# a2401-diode-distortion.net
KiCad netlist of a schematic drawn in EAGLE
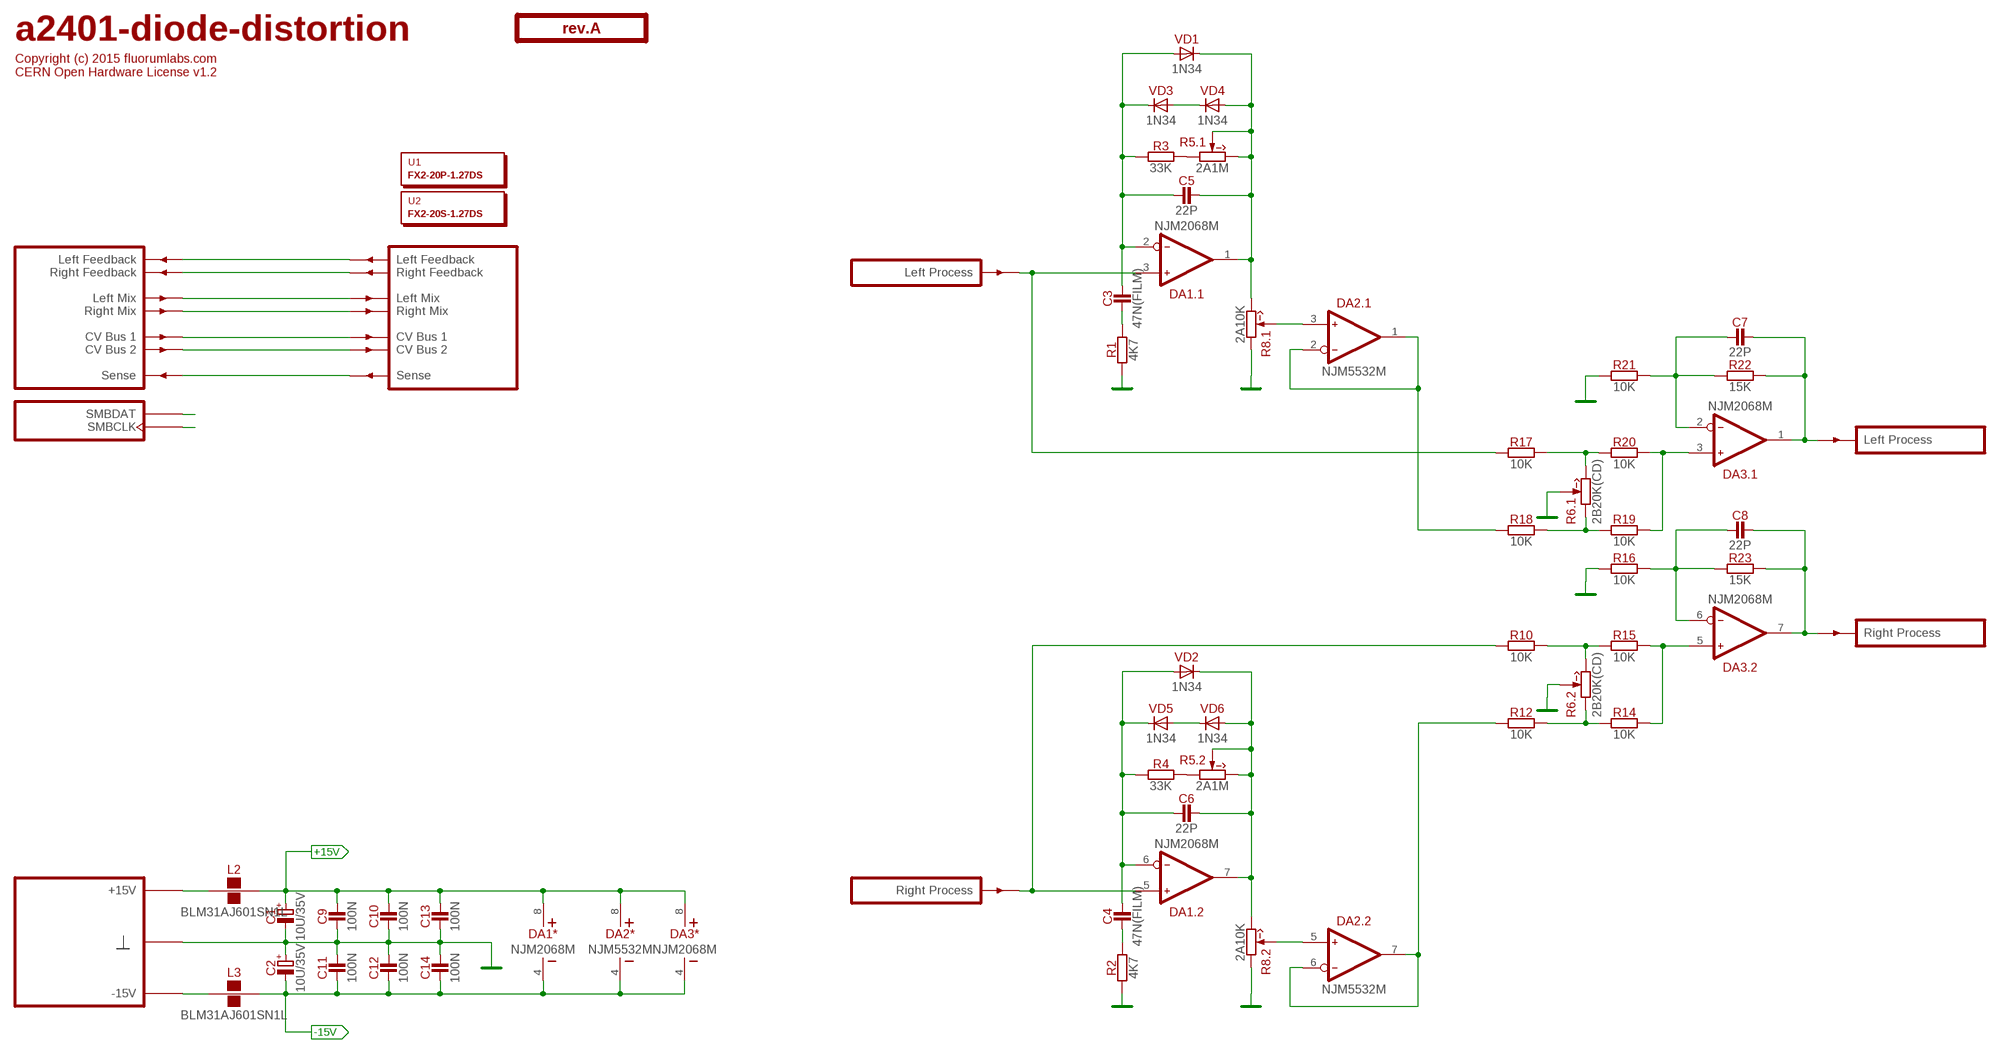
[diagram p0: schematic, sheet 1]

(export (version "E")
  (design (tool "Eeschema 10.0.6"))
  (components
    (comp (ref "C1")
      (value "10U/35V")
      (footprint "eagle-import:E2-5")
      (libsource (lib "eagle-import") (part "?10U/35V"))
    )
    (comp (ref "C2")
      (value "10U/35V")
      (footprint "eagle-import:E2-5")
      (libsource (lib "eagle-import") (part "?10U/35V"))
    )
    (comp (ref "C3")
      (value "47N(FILM)")
      (footprint "eagle-import:C050-025X075")
      (libsource (lib "eagle-import") (part "?47N(FILM)"))
    )
    (comp (ref "C4")
      (value "47N(FILM)")
      (footprint "eagle-import:C050-025X075")
      (libsource (lib "eagle-import") (part "?47N(FILM)"))
    )
    (comp (ref "C5")
      (value "22P")
      (footprint "eagle-import:C-0805")
      (libsource (lib "eagle-import") (part "?22P"))
    )
    (comp (ref "C6")
      (value "22P")
      (footprint "eagle-import:C-0805")
      (libsource (lib "eagle-import") (part "?22P"))
    )
    (comp (ref "C7")
      (value "22P")
      (footprint "eagle-import:C-0805")
      (libsource (lib "eagle-import") (part "?22P"))
    )
    (comp (ref "C8")
      (value "22P")
      (footprint "eagle-import:C-0805")
      (libsource (lib "eagle-import") (part "?22P"))
    )
    (comp (ref "C9")
      (value "100N")
      (footprint "eagle-import:C-0805")
      (libsource (lib "eagle-import") (part "?100N"))
    )
    (comp (ref "C10")
      (value "100N")
      (footprint "eagle-import:C-0805")
      (libsource (lib "eagle-import") (part "?100N"))
    )
    (comp (ref "C11")
      (value "100N")
      (footprint "eagle-import:C-0805")
      (libsource (lib "eagle-import") (part "?100N"))
    )
    (comp (ref "C12")
      (value "100N")
      (footprint "eagle-import:C-0805")
      (libsource (lib "eagle-import") (part "?100N"))
    )
    (comp (ref "C13")
      (value "100N")
      (footprint "eagle-import:C-0805")
      (libsource (lib "eagle-import") (part "?100N"))
    )
    (comp (ref "C14")
      (value "100N")
      (footprint "eagle-import:C-0805")
      (libsource (lib "eagle-import") (part "?100N"))
    )
    (comp (ref "DA1")
      (value "NJM2068M")
      (footprint "eagle-import:SO-8")
      (libsource (lib "eagle-import") (part "NJM2068M"))
    )
    (comp (ref "DA2")
      (value "NJM5532M")
      (footprint "eagle-import:SO-8")
      (libsource (lib "eagle-import") (part "NJM5532M"))
    )
    (comp (ref "DA3")
      (value "NJM2068M")
      (footprint "eagle-import:SO-8")
      (libsource (lib "eagle-import") (part "NJM2068M"))
    )
    (comp (ref "L2")
      (value "BLM31AJ601SN1L")
      (footprint "eagle-import:1206")
      (libsource (lib "eagle-import") (part "BLM31AJ601SN1L"))
    )
    (comp (ref "L3")
      (value "BLM31AJ601SN1L")
      (footprint "eagle-import:1206")
      (libsource (lib "eagle-import") (part "BLM31AJ601SN1L"))
    )
    (comp (ref "O1")
      (value "TITLE")
      (footprint "eagle-import:EMPTY")
      (libsource (lib "eagle-import") (part "TITLE"))
    )
    (comp (ref "PCB1")
      (value "rev.A")
      (footprint "eagle-import:ST2-BOARD-50")
      (libsource (lib "eagle-import") (part "ST2-BOARD-50"))
    )
    (comp (ref "R1")
      (value "4K7")
      (footprint "eagle-import:R-0805")
      (libsource (lib "eagle-import") (part "?4K7"))
    )
    (comp (ref "R2")
      (value "4K7")
      (footprint "eagle-import:R-0805")
      (libsource (lib "eagle-import") (part "?4K7"))
    )
    (comp (ref "R3")
      (value "33K")
      (footprint "eagle-import:R-0805")
      (libsource (lib "eagle-import") (part "?33K"))
    )
    (comp (ref "R4")
      (value "33K")
      (footprint "eagle-import:R-0805")
      (libsource (lib "eagle-import") (part "?33K"))
    )
    (comp (ref "R5")
      (value "2A1M")
      (footprint "eagle-import:RV11-DUAL")
      (libsource (lib "eagle-import") (part "2?A1M"))
    )
    (comp (ref "R6")
      (value "2B20K(CD)")
      (footprint "eagle-import:RV11-DUAL")
      (libsource (lib "eagle-import") (part "2?B20K(CD)"))
    )
    (comp (ref "R8")
      (value "2A10K")
      (footprint "eagle-import:RV11-DUAL")
      (libsource (lib "eagle-import") (part "2?A10K"))
    )
    (comp (ref "R10")
      (value "10K")
      (footprint "eagle-import:R-0805")
      (libsource (lib "eagle-import") (part "?10K"))
    )
    (comp (ref "R12")
      (value "10K")
      (footprint "eagle-import:R-0805")
      (libsource (lib "eagle-import") (part "?10K"))
    )
    (comp (ref "R14")
      (value "10K")
      (footprint "eagle-import:R-0805")
      (libsource (lib "eagle-import") (part "?10K"))
    )
    (comp (ref "R15")
      (value "10K")
      (footprint "eagle-import:R-0805")
      (libsource (lib "eagle-import") (part "?10K"))
    )
    (comp (ref "R16")
      (value "10K")
      (footprint "eagle-import:R-0805")
      (libsource (lib "eagle-import") (part "?10K"))
    )
    (comp (ref "R17")
      (value "10K")
      (footprint "eagle-import:R-0805")
      (libsource (lib "eagle-import") (part "?10K"))
    )
    (comp (ref "R18")
      (value "10K")
      (footprint "eagle-import:R-0805")
      (libsource (lib "eagle-import") (part "?10K"))
    )
    (comp (ref "R19")
      (value "10K")
      (footprint "eagle-import:R-0805")
      (libsource (lib "eagle-import") (part "?10K"))
    )
    (comp (ref "R20")
      (value "10K")
      (footprint "eagle-import:R-0805")
      (libsource (lib "eagle-import") (part "?10K"))
    )
    (comp (ref "R21")
      (value "10K")
      (footprint "eagle-import:R-0805")
      (libsource (lib "eagle-import") (part "?10K"))
    )
    (comp (ref "R22")
      (value "15K")
      (footprint "eagle-import:R-0805")
      (libsource (lib "eagle-import") (part "?15K"))
    )
    (comp (ref "R23")
      (value "15K")
      (footprint "eagle-import:R-0805")
      (libsource (lib "eagle-import") (part "?15K"))
    )
    (comp (ref "U1")
      (value "FX2-20P-1.27DS")
      (footprint "eagle-import:EMPTY")
      (libsource (lib "eagle-import") (part "?FX2-20P-1.27DS"))
    )
    (comp (ref "U2")
      (value "FX2-20S-1.27DS")
      (footprint "eagle-import:EMPTY")
      (libsource (lib "eagle-import") (part "?FX2-20S-1.27DS"))
    )
    (comp (ref "VD1")
      (value "1N34")
      (footprint "eagle-import:DO35-15")
      (libsource (lib "eagle-import") (part "?1N34"))
    )
    (comp (ref "VD2")
      (value "1N34")
      (footprint "eagle-import:DO35-15")
      (libsource (lib "eagle-import") (part "?1N34"))
    )
    (comp (ref "VD3")
      (value "1N34")
      (footprint "eagle-import:DO35-15")
      (libsource (lib "eagle-import") (part "?1N34"))
    )
    (comp (ref "VD4")
      (value "1N34")
      (footprint "eagle-import:DO35-15")
      (libsource (lib "eagle-import") (part "?1N34"))
    )
    (comp (ref "VD5")
      (value "1N34")
      (footprint "eagle-import:DO35-15")
      (libsource (lib "eagle-import") (part "?1N34"))
    )
    (comp (ref "VD6")
      (value "1N34")
      (footprint "eagle-import:DO35-15")
      (libsource (lib "eagle-import") (part "?1N34"))
    )
  )
  (nets
    (net (code "1") (name "+15V") (class "Default")
      (node (ref "C1") (pin "+") (pinfunction "+_+") (pintype "passive"))
      (node (ref "C10") (pin "2") (pinfunction "2_2") (pintype "passive"))
      (node (ref "C13") (pin "2") (pinfunction "2_2") (pintype "passive"))
      (node (ref "C9") (pin "2") (pinfunction "2_2") (pintype "passive"))
      (node (ref "DA1") (pin "8") (pinfunction "V+_8") (pintype "power_in"))
      (node (ref "DA2") (pin "8") (pinfunction "V+_8") (pintype "power_in"))
      (node (ref "DA3") (pin "8") (pinfunction "V+_8") (pintype "power_in"))
      (node (ref "L2") (pin "2") (pinfunction "2_2") (pintype "passive"))
    )
    (net (code "2") (name "-15V") (class "Default")
      (node (ref "C11") (pin "1") (pinfunction "1_1") (pintype "passive"))
      (node (ref "C12") (pin "1") (pinfunction "1_1") (pintype "passive"))
      (node (ref "C14") (pin "1") (pinfunction "1_1") (pintype "passive"))
      (node (ref "C2") (pin "-") (pinfunction "-_-") (pintype "passive"))
      (node (ref "DA1") (pin "4") (pinfunction "V-_4") (pintype "power_in"))
      (node (ref "DA2") (pin "4") (pinfunction "V-_4") (pintype "power_in"))
      (node (ref "DA3") (pin "4") (pinfunction "V-_4") (pintype "power_in"))
      (node (ref "L3") (pin "2") (pinfunction "2_2") (pintype "passive"))
    )
    (net (code "3") (name "GND") (class "Default")
      (node (ref "C1") (pin "-") (pinfunction "-_-") (pintype "passive"))
      (node (ref "C10") (pin "1") (pinfunction "1_1") (pintype "passive"))
      (node (ref "C11") (pin "2") (pinfunction "2_2") (pintype "passive"))
      (node (ref "C12") (pin "2") (pinfunction "2_2") (pintype "passive"))
      (node (ref "C13") (pin "1") (pinfunction "1_1") (pintype "passive"))
      (node (ref "C14") (pin "2") (pinfunction "2_2") (pintype "passive"))
      (node (ref "C2") (pin "+") (pinfunction "+_+") (pintype "passive"))
      (node (ref "C9") (pin "1") (pinfunction "1_1") (pintype "passive"))
      (node (ref "PCB1") (pin "B4") (pinfunction "GND_B4") (pintype "bidirectional"))
      (node (ref "PCB1") (pin "B4'") (pinfunction "GND_B4'") (pintype "bidirectional"))
      (node (ref "PCB1") (pin "B5") (pinfunction "GND_B5") (pintype "bidirectional"))
      (node (ref "PCB1") (pin "B5'") (pinfunction "GND_B5'") (pintype "bidirectional"))
      (node (ref "PCB1") (pin "B6") (pinfunction "GND_B6") (pintype "bidirectional"))
      (node (ref "PCB1") (pin "B6'") (pinfunction "GND_B6'") (pintype "bidirectional"))
      (node (ref "PCB1") (pin "B7") (pinfunction "GND_B7") (pintype "bidirectional"))
      (node (ref "PCB1") (pin "B7'") (pinfunction "GND_B7'") (pintype "bidirectional"))
      (node (ref "PCB1") (pin "B8") (pinfunction "GND_B8") (pintype "bidirectional"))
      (node (ref "PCB1") (pin "B8'") (pinfunction "GND_B8'") (pintype "bidirectional"))
      (node (ref "R1") (pin "1") (pinfunction "1_1") (pintype "passive"))
      (node (ref "R16") (pin "1") (pinfunction "1_1") (pintype "passive"))
      (node (ref "R2") (pin "1") (pinfunction "1_1") (pintype "passive"))
      (node (ref "R21") (pin "1") (pinfunction "1_1") (pintype "passive"))
      (node (ref "R6") (pin "2") (pinfunction "W_2") (pintype "passive"))
      (node (ref "R6") (pin "2'") (pinfunction "W_2'") (pintype "passive"))
      (node (ref "R8") (pin "1") (pinfunction "CCW_1") (pintype "passive"))
      (node (ref "R8") (pin "1'") (pinfunction "CCW_1'") (pintype "passive"))
    )
    (net (code "4") (name "Net-(C3-Pad1)") (class "Default")
      (node (ref "C3") (pin "1") (pinfunction "1_1") (pintype "passive"))
      (node (ref "R1") (pin "2") (pinfunction "2_2") (pintype "passive"))
    )
    (net (code "5") (name "Net-(C4-Pad1)") (class "Default")
      (node (ref "C4") (pin "1") (pinfunction "1_1") (pintype "passive"))
      (node (ref "R2") (pin "2") (pinfunction "2_2") (pintype "passive"))
    )
    (net (code "6") (name "Net-(DA1B-IN+)") (class "Default")
      (node (ref "DA1") (pin "3") (pinfunction "IN+_3") (pintype "input"))
      (node (ref "PCB1") (pin "BINL") (pinfunction "INL_BINL") (pintype "bidirectional"))
      (node (ref "R17") (pin "1") (pinfunction "1_1") (pintype "passive"))
    )
    (net (code "7") (name "Net-(DA1B-IN-)") (class "Default")
      (node (ref "C3") (pin "2") (pinfunction "2_2") (pintype "passive"))
      (node (ref "C5") (pin "1") (pinfunction "1_1") (pintype "passive"))
      (node (ref "DA1") (pin "2") (pinfunction "IN-_2") (pintype "input"))
      (node (ref "R3") (pin "1") (pinfunction "1_1") (pintype "passive"))
      (node (ref "VD1") (pin "A") (pinfunction "A_A") (pintype "passive"))
      (node (ref "VD3") (pin "C") (pinfunction "C_C") (pintype "passive"))
    )
    (net (code "8") (name "Net-(DA1B-OUT)") (class "Default")
      (node (ref "C5") (pin "2") (pinfunction "2_2") (pintype "passive"))
      (node (ref "DA1") (pin "1") (pinfunction "OUT_1") (pintype "output"))
      (node (ref "R5") (pin "2") (pinfunction "W_2") (pintype "passive"))
      (node (ref "R5") (pin "3") (pinfunction "CW_3") (pintype "passive"))
      (node (ref "R8") (pin "3") (pinfunction "CW_3") (pintype "passive"))
      (node (ref "VD1") (pin "C") (pinfunction "C_C") (pintype "passive"))
      (node (ref "VD4") (pin "A") (pinfunction "A_A") (pintype "passive"))
    )
    (net (code "9") (name "Net-(DA1C-IN+)") (class "Default")
      (node (ref "DA1") (pin "5") (pinfunction "IN+_5") (pintype "input"))
      (node (ref "PCB1") (pin "BINR") (pinfunction "INR_BINR") (pintype "bidirectional"))
      (node (ref "R10") (pin "1") (pinfunction "1_1") (pintype "passive"))
    )
    (net (code "10") (name "Net-(DA1C-IN-)") (class "Default")
      (node (ref "C4") (pin "2") (pinfunction "2_2") (pintype "passive"))
      (node (ref "C6") (pin "1") (pinfunction "1_1") (pintype "passive"))
      (node (ref "DA1") (pin "6") (pinfunction "IN-_6") (pintype "input"))
      (node (ref "R4") (pin "1") (pinfunction "1_1") (pintype "passive"))
      (node (ref "VD2") (pin "A") (pinfunction "A_A") (pintype "passive"))
      (node (ref "VD5") (pin "C") (pinfunction "C_C") (pintype "passive"))
    )
    (net (code "11") (name "Net-(DA1C-OUT)") (class "Default")
      (node (ref "C6") (pin "2") (pinfunction "2_2") (pintype "passive"))
      (node (ref "DA1") (pin "7") (pinfunction "OUT_7") (pintype "output"))
      (node (ref "R5") (pin "2'") (pinfunction "W_2'") (pintype "passive"))
      (node (ref "R5") (pin "3'") (pinfunction "CW_3'") (pintype "passive"))
      (node (ref "R8") (pin "3'") (pinfunction "CW_3'") (pintype "passive"))
      (node (ref "VD2") (pin "C") (pinfunction "C_C") (pintype "passive"))
      (node (ref "VD6") (pin "A") (pinfunction "A_A") (pintype "passive"))
    )
    (net (code "12") (name "Net-(DA2B-IN+)") (class "Default")
      (node (ref "DA2") (pin "3") (pinfunction "IN+_3") (pintype "input"))
      (node (ref "R8") (pin "2") (pinfunction "W_2") (pintype "passive"))
    )
    (net (code "13") (name "Net-(DA2B-IN-)") (class "Default")
      (node (ref "DA2") (pin "1") (pinfunction "OUT_1") (pintype "output"))
      (node (ref "DA2") (pin "2") (pinfunction "IN-_2") (pintype "input"))
      (node (ref "R18") (pin "1") (pinfunction "1_1") (pintype "passive"))
    )
    (net (code "14") (name "Net-(DA2C-IN+)") (class "Default")
      (node (ref "DA2") (pin "5") (pinfunction "IN+_5") (pintype "input"))
      (node (ref "R8") (pin "2'") (pinfunction "W_2'") (pintype "passive"))
    )
    (net (code "15") (name "Net-(DA2C-IN-)") (class "Default")
      (node (ref "DA2") (pin "6") (pinfunction "IN-_6") (pintype "input"))
      (node (ref "DA2") (pin "7") (pinfunction "OUT_7") (pintype "output"))
      (node (ref "R12") (pin "1") (pinfunction "1_1") (pintype "passive"))
    )
    (net (code "16") (name "Net-(DA3B-IN+)") (class "Default")
      (node (ref "DA3") (pin "3") (pinfunction "IN+_3") (pintype "input"))
      (node (ref "R19") (pin "2") (pinfunction "2_2") (pintype "passive"))
      (node (ref "R20") (pin "2") (pinfunction "2_2") (pintype "passive"))
    )
    (net (code "17") (name "Net-(DA3B-IN-)") (class "Default")
      (node (ref "C7") (pin "1") (pinfunction "1_1") (pintype "passive"))
      (node (ref "DA3") (pin "2") (pinfunction "IN-_2") (pintype "input"))
      (node (ref "R21") (pin "2") (pinfunction "2_2") (pintype "passive"))
      (node (ref "R22") (pin "1") (pinfunction "1_1") (pintype "passive"))
    )
    (net (code "18") (name "Net-(DA3B-OUT)") (class "Default")
      (node (ref "C7") (pin "2") (pinfunction "2_2") (pintype "passive"))
      (node (ref "DA3") (pin "1") (pinfunction "OUT_1") (pintype "output"))
      (node (ref "PCB1") (pin "BOUTL'") (pinfunction "OUTL_BOUTL'") (pintype "bidirectional"))
      (node (ref "R22") (pin "2") (pinfunction "2_2") (pintype "passive"))
    )
    (net (code "19") (name "Net-(DA3C-IN+)") (class "Default")
      (node (ref "DA3") (pin "5") (pinfunction "IN+_5") (pintype "input"))
      (node (ref "R14") (pin "2") (pinfunction "2_2") (pintype "passive"))
      (node (ref "R15") (pin "2") (pinfunction "2_2") (pintype "passive"))
    )
    (net (code "20") (name "Net-(DA3C-IN-)") (class "Default")
      (node (ref "C8") (pin "1") (pinfunction "1_1") (pintype "passive"))
      (node (ref "DA3") (pin "6") (pinfunction "IN-_6") (pintype "input"))
      (node (ref "R16") (pin "2") (pinfunction "2_2") (pintype "passive"))
      (node (ref "R23") (pin "1") (pinfunction "1_1") (pintype "passive"))
    )
    (net (code "21") (name "Net-(DA3C-OUT)") (class "Default")
      (node (ref "C8") (pin "2") (pinfunction "2_2") (pintype "passive"))
      (node (ref "DA3") (pin "7") (pinfunction "OUT_7") (pintype "output"))
      (node (ref "PCB1") (pin "BOUTR'") (pinfunction "OUTR_BOUTR'") (pintype "bidirectional"))
      (node (ref "R23") (pin "2") (pinfunction "2_2") (pintype "passive"))
    )
    (net (code "22") (name "Net-(L2-Pad1)") (class "Default")
      (node (ref "L2") (pin "1") (pinfunction "1_1") (pintype "passive"))
      (node (ref "PCB1") (pin "A+15") (pinfunction "P+15V_A+15") (pintype "bidirectional"))
      (node (ref "PCB1") (pin "A+15'") (pinfunction "P+15V_A+15'") (pintype "bidirectional"))
      (node (ref "PCB1") (pin "B+15") (pinfunction "P+15V_B+15") (pintype "bidirectional"))
      (node (ref "PCB1") (pin "B+15'") (pinfunction "P+15V_B+15'") (pintype "bidirectional"))
    )
    (net (code "23") (name "Net-(L3-Pad1)") (class "Default")
      (node (ref "L3") (pin "1") (pinfunction "1_1") (pintype "passive"))
      (node (ref "PCB1") (pin "A-15") (pinfunction "P-15V_A-15") (pintype "bidirectional"))
      (node (ref "PCB1") (pin "A-15'") (pinfunction "P-15V_A-15'") (pintype "bidirectional"))
      (node (ref "PCB1") (pin "B-15") (pinfunction "P-15V_B-15") (pintype "bidirectional"))
      (node (ref "PCB1") (pin "B-15'") (pinfunction "P-15V_B-15'") (pintype "bidirectional"))
    )
    (net (code "24") (name "Net-(PCB1F-CV1)") (class "Default")
      (node (ref "PCB1") (pin "ACV1") (pinfunction "CV1_ACV1") (pintype "bidirectional"))
      (node (ref "PCB1") (pin "ACV1'") (pinfunction "CV1'_ACV1'") (pintype "bidirectional"))
    )
    (net (code "25") (name "Net-(PCB1F-CV2)") (class "Default")
      (node (ref "PCB1") (pin "ACV2") (pinfunction "CV2_ACV2") (pintype "bidirectional"))
      (node (ref "PCB1") (pin "ACV2'") (pinfunction "CV2'_ACV2'") (pintype "bidirectional"))
    )
    (net (code "26") (name "Net-(PCB1F-LFBK)") (class "Default")
      (node (ref "PCB1") (pin "ALFBK") (pinfunction "LFBK_ALFBK") (pintype "bidirectional"))
      (node (ref "PCB1") (pin "ALFBK'") (pinfunction "LFBK'_ALFBK'") (pintype "bidirectional"))
    )
    (net (code "27") (name "Net-(PCB1F-LMIX)") (class "Default")
      (node (ref "PCB1") (pin "ALMIX") (pinfunction "LMIX_ALMIX") (pintype "bidirectional"))
      (node (ref "PCB1") (pin "ALMIX'") (pinfunction "LMIX'_ALMIX'") (pintype "bidirectional"))
    )
    (net (code "28") (name "Net-(PCB1F-RFBK)") (class "Default")
      (node (ref "PCB1") (pin "ARFBK") (pinfunction "RFBK_ARFBK") (pintype "bidirectional"))
      (node (ref "PCB1") (pin "ARFBK'") (pinfunction "RFBK'_ARFBK'") (pintype "bidirectional"))
    )
    (net (code "29") (name "Net-(PCB1F-RMIX)") (class "Default")
      (node (ref "PCB1") (pin "ARMIX") (pinfunction "RMIX_ARMIX") (pintype "bidirectional"))
      (node (ref "PCB1") (pin "ARMIX'") (pinfunction "RMIX'_ARMIX'") (pintype "bidirectional"))
    )
    (net (code "30") (name "Net-(PCB1F-SENSE)") (class "Default")
      (node (ref "PCB1") (pin "BSENSE") (pinfunction "SENSE_BSENSE") (pintype "bidirectional"))
      (node (ref "PCB1") (pin "BSENSE'") (pinfunction "SENSE'_BSENSE'") (pintype "bidirectional"))
    )
    (net (code "31") (name "Net-(PCB1H-SMBCLK-PadASMBCLK')") (class "Default")
      (node (ref "PCB1") (pin "ASMBCLK") (pinfunction "SMBCLK_ASMBCLK") (pintype "bidirectional"))
      (node (ref "PCB1") (pin "ASMBCLK'") (pinfunction "SMBCLK_ASMBCLK'") (pintype "bidirectional"))
    )
    (net (code "32") (name "Net-(PCB1H-SMBDAT-PadASMBDAT')") (class "Default")
      (node (ref "PCB1") (pin "ASMBDAT") (pinfunction "SMBDAT_ASMBDAT") (pintype "bidirectional"))
      (node (ref "PCB1") (pin "ASMBDAT'") (pinfunction "SMBDAT_ASMBDAT'") (pintype "bidirectional"))
    )
    (net (code "33") (name "Net-(R5A-CCW)") (class "Default")
      (node (ref "R3") (pin "2") (pinfunction "2_2") (pintype "passive"))
      (node (ref "R5") (pin "1") (pinfunction "CCW_1") (pintype "passive"))
    )
    (net (code "34") (name "Net-(R5B-CCW)") (class "Default")
      (node (ref "R4") (pin "2") (pinfunction "2_2") (pintype "passive"))
      (node (ref "R5") (pin "1'") (pinfunction "CCW_1'") (pintype "passive"))
    )
    (net (code "35") (name "Net-(R6A-CCW)") (class "Default")
      (node (ref "R18") (pin "2") (pinfunction "2_2") (pintype "passive"))
      (node (ref "R19") (pin "1") (pinfunction "1_1") (pintype "passive"))
      (node (ref "R6") (pin "1") (pinfunction "CCW_1") (pintype "passive"))
    )
    (net (code "36") (name "Net-(R6A-CW)") (class "Default")
      (node (ref "R17") (pin "2") (pinfunction "2_2") (pintype "passive"))
      (node (ref "R20") (pin "1") (pinfunction "1_1") (pintype "passive"))
      (node (ref "R6") (pin "3") (pinfunction "CW_3") (pintype "passive"))
    )
    (net (code "37") (name "Net-(R6B-CCW)") (class "Default")
      (node (ref "R12") (pin "2") (pinfunction "2_2") (pintype "passive"))
      (node (ref "R14") (pin "1") (pinfunction "1_1") (pintype "passive"))
      (node (ref "R6") (pin "1'") (pinfunction "CCW_1'") (pintype "passive"))
    )
    (net (code "38") (name "Net-(R6B-CW)") (class "Default")
      (node (ref "R10") (pin "2") (pinfunction "2_2") (pintype "passive"))
      (node (ref "R15") (pin "1") (pinfunction "1_1") (pintype "passive"))
      (node (ref "R6") (pin "3'") (pinfunction "CW_3'") (pintype "passive"))
    )
    (net (code "39") (name "Net-(VD3-PadA)") (class "Default")
      (node (ref "VD3") (pin "A") (pinfunction "A_A") (pintype "passive"))
      (node (ref "VD4") (pin "C") (pinfunction "C_C") (pintype "passive"))
    )
    (net (code "40") (name "Net-(VD5-PadA)") (class "Default")
      (node (ref "VD5") (pin "A") (pinfunction "A_A") (pintype "passive"))
      (node (ref "VD6") (pin "C") (pinfunction "C_C") (pintype "passive"))
    )
  )
)
